# Power.net
KiCad netlist of a schematic drawn in Altium Designer
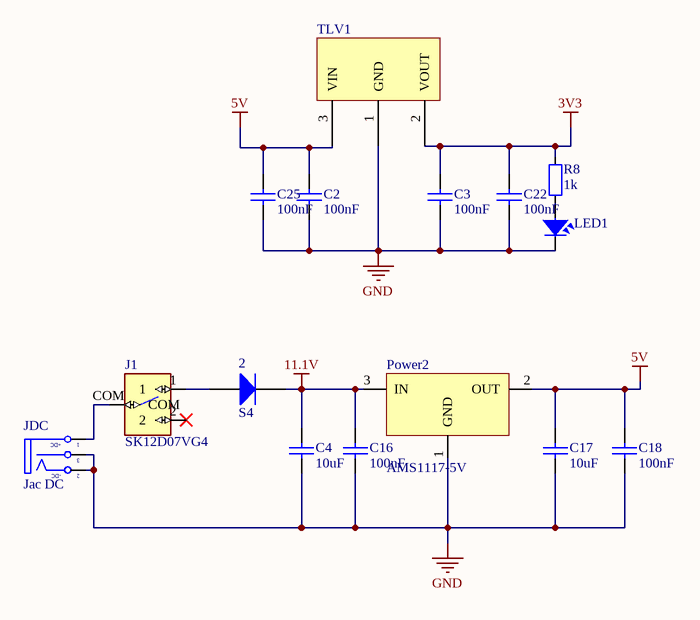
[diagram p0: Power.SchDoc]

(export (version "E")
  (design (tool "Eeschema 10.0.6"))
  (components
    (comp (ref "2")
      (value "S4")
      (footprint "DIO-214AC(SMA)")
      (description "Dán")
      (libsource (lib "THU VIEN SCH") (part "Diode S4"))
    )
    (comp (ref "C2")
      (value "100nF")
      (footprint "CAP_0805")
      (description "Capacitor")
      (fields (field (name "PUBLISHER") "Altium Limited"))
      (libsource (lib "My Library") (part "CapSMD"))
    )
    (comp (ref "C3")
      (value "100nF")
      (footprint "CAP_0805")
      (description "Capacitor")
      (fields (field (name "PUBLISHER") "Altium Limited"))
      (libsource (lib "My Library") (part "CapSMD"))
    )
    (comp (ref "C4")
      (value "10uF")
      (footprint "CAP_0805")
      (description "Capacitor")
      (fields (field (name "PUBLISHER") "Altium Limited"))
      (libsource (lib "My Library") (part "CapSMD"))
    )
    (comp (ref "C16")
      (value "100nF")
      (footprint "CAP_0805")
      (description "Capacitor")
      (fields (field (name "PUBLISHER") "Altium Limited"))
      (libsource (lib "My Library") (part "CapSMD"))
    )
    (comp (ref "C17")
      (value "10uF")
      (footprint "CAP_0805")
      (description "Capacitor")
      (fields (field (name "PUBLISHER") "Altium Limited"))
      (libsource (lib "My Library") (part "CapSMD"))
    )
    (comp (ref "C18")
      (value "100nF")
      (footprint "CAP_0805")
      (description "Capacitor")
      (fields (field (name "PUBLISHER") "Altium Limited"))
      (libsource (lib "My Library") (part "CapSMD"))
    )
    (comp (ref "C22")
      (value "100nF")
      (footprint "CAP_0805")
      (description "Capacitor")
      (fields (field (name "PUBLISHER") "Altium Limited"))
      (libsource (lib "My Library") (part "CapSMD"))
    )
    (comp (ref "C25")
      (value "100nF")
      (footprint "CAP_0805")
      (description "Capacitor")
      (fields (field (name "PUBLISHER") "Altium Limited"))
      (libsource (lib "My Library") (part "CapSMD"))
    )
    (comp (ref "J1")
      (value "SK12D07VG4")
      (footprint "SK12D07VG4")
      (description "Switch Slide ON ON SPDT Side Slide 0.3A 30VDC PC Pins Bracket Mount/Through Hole Bulk")
      (fields (field (name "MF") "C&K"))
      (libsource (lib "SK12D07VG4") (part "SK12D07VG4"))
    )
    (comp (ref "JDC")
      (value "Jac DC")
      (footprint "DC-IN")
      (description "Jac DC input")
      (libsource (lib "My Library") (part "DCIN"))
    )
    (comp (ref "LED1")
      (value "LED")
      (footprint "LED-0805-Blue")
      (description "LED Single colour Green and Red")
      (libsource (lib "My Library") (part "LED"))
    )
    (comp (ref "Power2")
      (value "AMS1117-5V")
      (footprint "SOT223")
      (description "800mA Low-Dropout Linear Regulator")
      (fields (field (name "CREATOR") "Nguyen Ba Bien"))
      (libsource (lib "LIBRARY1") (part "LM1117"))
    )
    (comp (ref "R8")
      (value "1k")
      (footprint "RES-SMD-0805")
      (description "Resistor")
      (fields
        (field (name "MANUFACTURER") "Generic Components")
        (field (name "PUBLISHER") "Altium Hobart Technology Centre")
      )
      (libsource (lib "My Library") (part "Resistor - SMD"))
    )
    (comp (ref "TLV1")
      (value "LM1117- 5V")
      (footprint "SOT230P700X180-4N")
      (libsource (lib "hphonglib") (part "LM1117"))
    )
  )
  (nets
    (net (code "1") (name "3V3") (class "Default")
      (node (ref "C22") (pin "1") (pinfunction "1_1") (pintype "passive"))
      (node (ref "C3") (pin "1") (pinfunction "1_1") (pintype "passive"))
      (node (ref "R8") (pin "1") (pinfunction "1_1") (pintype "passive"))
      (node (ref "TLV1") (pin "2") (pinfunction "VOUT_2") (pintype "passive"))
    )
    (net (code "2") (name "5V") (class "Default")
      (node (ref "C17") (pin "1") (pinfunction "1_1") (pintype "passive"))
      (node (ref "C18") (pin "1") (pinfunction "1_1") (pintype "passive"))
      (node (ref "C2") (pin "1") (pinfunction "1_1") (pintype "passive"))
      (node (ref "C25") (pin "1") (pinfunction "1_1") (pintype "passive"))
      (node (ref "Power2") (pin "2") (pinfunction "OUT_2") (pintype "passive"))
      (node (ref "TLV1") (pin "3") (pinfunction "VIN_3") (pintype "passive"))
    )
    (net (code "3") (name "11.1V") (class "Default")
      (node (ref "2") (pin "2") (pinfunction "K_2") (pintype "passive"))
      (node (ref "C16") (pin "1") (pinfunction "1_1") (pintype "passive"))
      (node (ref "C4") (pin "1") (pinfunction "1_1") (pintype "passive"))
      (node (ref "Power2") (pin "3") (pinfunction "IN_3") (pintype "passive"))
    )
    (net (code "4") (name "GND") (class "Default")
      (node (ref "C16") (pin "2") (pinfunction "2_2") (pintype "passive"))
      (node (ref "C17") (pin "2") (pinfunction "2_2") (pintype "passive"))
      (node (ref "C18") (pin "2") (pinfunction "2_2") (pintype "passive"))
      (node (ref "C2") (pin "2") (pinfunction "2_2") (pintype "passive"))
      (node (ref "C22") (pin "2") (pinfunction "2_2") (pintype "passive"))
      (node (ref "C25") (pin "2") (pinfunction "2_2") (pintype "passive"))
      (node (ref "C3") (pin "2") (pinfunction "2_2") (pintype "passive"))
      (node (ref "C4") (pin "2") (pinfunction "2_2") (pintype "passive"))
      (node (ref "JDC") (pin "2") (pinfunction "TN_2") (pintype "passive"))
      (node (ref "JDC") (pin "3") (pinfunction "S_3") (pintype "power_in"))
      (node (ref "LED1") (pin "2") (pinfunction "2_2") (pintype "passive"))
      (node (ref "Power2") (pin "1") (pinfunction "GND_1") (pintype "passive"))
      (node (ref "TLV1") (pin "1") (pinfunction "GND_1") (pintype "passive"))
    )
    (net (code "5") (name "Net-(2-A)") (class "Default")
      (node (ref "2") (pin "1") (pinfunction "A_1") (pintype "passive"))
      (node (ref "J1") (pin "1") (pinfunction "1_1") (pintype "bidirectional"))
    )
    (net (code "6") (name "Net-(JDC-T)") (class "Default")
      (node (ref "J1") (pin "COM") (pinfunction "COM_COM") (pintype "bidirectional"))
      (node (ref "JDC") (pin "1") (pinfunction "T_1") (pintype "passive"))
    )
    (net (code "7") (name "Net-(LED1-Pad1)") (class "Default")
      (node (ref "LED1") (pin "1") (pinfunction "1_1") (pintype "passive"))
      (node (ref "R8") (pin "2") (pinfunction "2_2") (pintype "passive"))
    )
    (net (code "8") (name "unconnected-(J1-Pad2)") (class "Default")
      (node (ref "J1") (pin "2") (pinfunction "2_2") (pintype "bidirectional+no_connect"))
    )
  )
)
